# red.net
KiCad netlist of a schematic drawn in Altium Designer
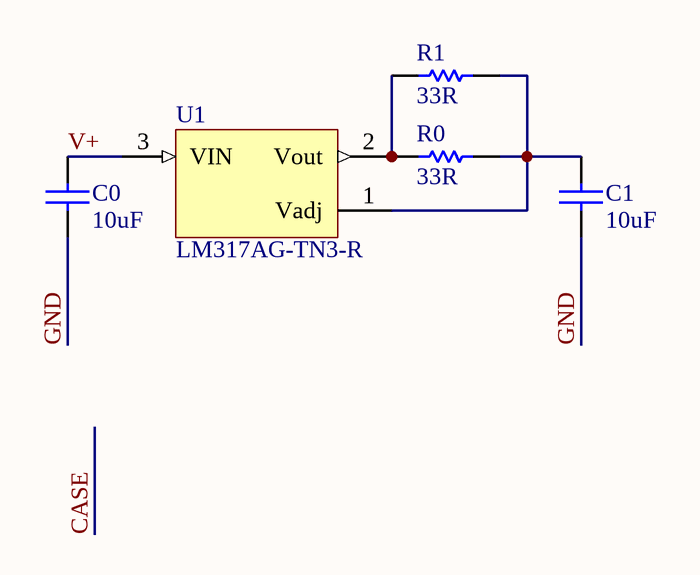
[diagram p0: red.SchDoc]

(export (version "E")
  (design (tool "Eeschema 10.0.6"))
  (components
    (comp (ref "C0")
      (value "10uF")
      (footprint "C_0805")
      (description "C - CAPACITOR - MLCC - 10uF - 25V - 0805")
      (fields (field (name "LCSC PART #") "C15850") (field (name "Comment") "CL21A106KAYNNNE"))
      (libsource (lib "JLC_PCB") (part "CL21A106KAYNNNE"))
    )
    (comp (ref "C1")
      (value "10uF")
      (footprint "C_0805")
      (description "C - CAPACITOR - MLCC - 10uF - 25V - 0805")
      (fields (field (name "LCSC PART #") "C15850") (field (name "Comment") "CL21A106KAYNNNE"))
      (libsource (lib "JLC_PCB") (part "CL21A106KAYNNNE"))
    )
    (comp (ref "R0")
      (value "33R")
      (footprint "R_0805")
      (description "R - RESISTOR - SMD - 33R - 1% - 0402")
      (fields (field (name "LCSC PART #") "C17634") (field (name "Comment") "0805W8F330JT5E"))
      (libsource (lib "JLC_PCB") (part "0805W8F330JT5E"))
    )
    (comp (ref "R1")
      (value "33R")
      (footprint "R_0805")
      (description "R - RESISTOR - SMD - 33R - 1% - 0402")
      (fields (field (name "LCSC PART #") "C17634") (field (name "Comment") "0805W8F330JT5E"))
      (libsource (lib "JLC_PCB") (part "0805W8F330JT5E"))
    )
    (comp (ref "U1")
      (value "LM317AG-TN3-R")
      (footprint "TO-252AA")
      (description "U - IC - ADJUSTABLE LDO")
      (fields (field (name "LCSC PART #") "C75510"))
      (libsource (lib "JLC_PCB") (part "LM317AG-TN3-R"))
    )
  )
  (nets
    (net (code "2") (name "/GND") (class "Default")
      (node (ref "C0") (pin "1") (pinfunction "1_1") (pintype "passive"))
      (node (ref "C1") (pin "1") (pinfunction "1_1") (pintype "passive"))
    )
    (net (code "3") (name "/V+") (class "Default")
      (node (ref "C0") (pin "2") (pinfunction "2_2") (pintype "passive"))
      (node (ref "U1") (pin "3") (pinfunction "VIN_3") (pintype "input"))
    )
    (net (code "4") (name "Net-(U1-Vadj)") (class "Default")
      (node (ref "C1") (pin "2") (pinfunction "2_2") (pintype "passive"))
      (node (ref "R0") (pin "2") (pinfunction "2_2") (pintype "passive"))
      (node (ref "R1") (pin "2") (pinfunction "2_2") (pintype "passive"))
      (node (ref "U1") (pin "1") (pinfunction "Vadj_1") (pintype "power_in"))
    )
    (net (code "5") (name "Net-(U1-Vout)") (class "Default")
      (node (ref "R0") (pin "1") (pinfunction "1_1") (pintype "passive"))
      (node (ref "R1") (pin "1") (pinfunction "1_1") (pintype "passive"))
      (node (ref "U1") (pin "2") (pinfunction "Vout_2") (pintype "output"))
    )
  )
)
